# 04_MICROCONTROLLER.net
KiCad netlist of a schematic drawn in Altium Designer
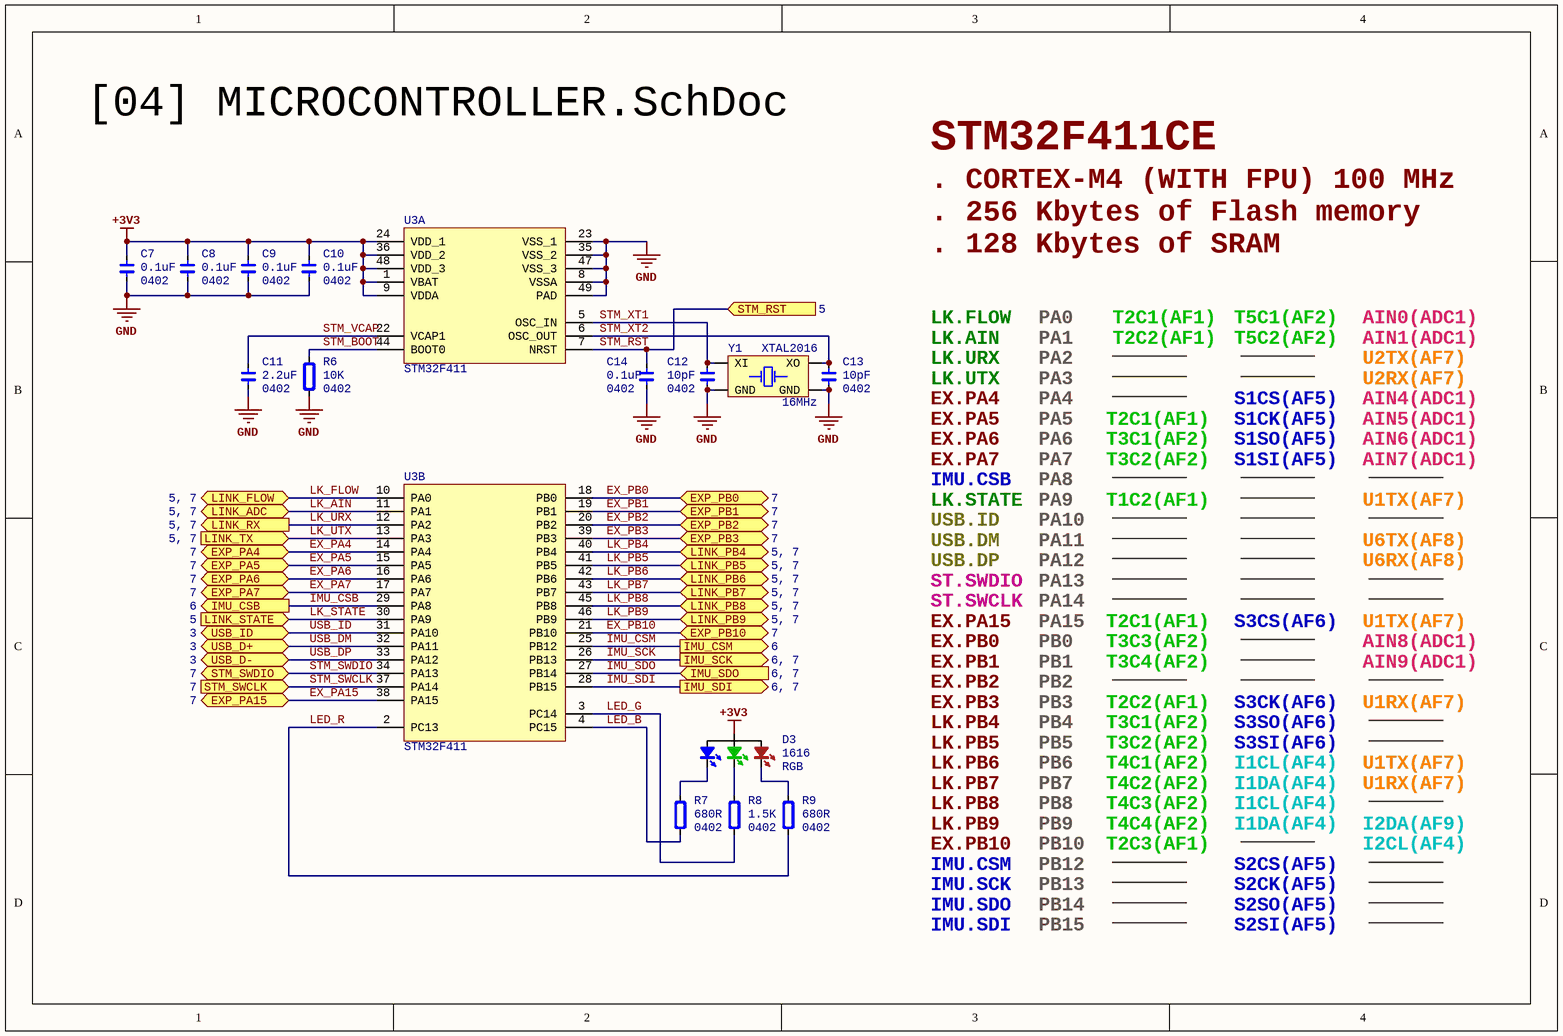
[diagram p0: [04] MICROCONTROLLER.SchDoc]

(export (version "E")
  (design (tool "Eeschema 10.0.6"))
  (components
    (comp (ref "C7")
      (value "0.1uF")
      (footprint "PCB_PassiveCap:CAP_0402")
      (description "Capacitor")
      (fields (field (name "TYPE") "0402") (field (name "Comment") "C0402"))
      (libsource (lib "SCH_Passive") (part "Cap_0402"))
    )
    (comp (ref "C8")
      (value "0.1uF")
      (footprint "PCB_PassiveCap:CAP_0402")
      (description "Capacitor")
      (fields (field (name "TYPE") "0402") (field (name "Comment") "C0402"))
      (libsource (lib "SCH_Passive") (part "Cap_0402"))
    )
    (comp (ref "C9")
      (value "0.1uF")
      (footprint "PCB_PassiveCap:CAP_0402")
      (description "Capacitor")
      (fields (field (name "TYPE") "0402") (field (name "Comment") "C0402"))
      (libsource (lib "SCH_Passive") (part "Cap_0402"))
    )
    (comp (ref "C10")
      (value "0.1uF")
      (footprint "PCB_PassiveCap:CAP_0402")
      (description "Capacitor")
      (fields (field (name "TYPE") "0402") (field (name "Comment") "C0402"))
      (libsource (lib "SCH_Passive") (part "Cap_0402"))
    )
    (comp (ref "C11")
      (value "2.2uF")
      (footprint "PCB_PassiveCap:CAP_0402")
      (description "Capacitor")
      (fields (field (name "TYPE") "0402") (field (name "Comment") "C0402"))
      (libsource (lib "SCH_Passive") (part "Cap_0402"))
    )
    (comp (ref "C12")
      (value "10pF")
      (footprint "PCB_PassiveCap:CAP_0402")
      (description "Capacitor")
      (fields (field (name "TYPE") "0402") (field (name "Comment") "C0402"))
      (libsource (lib "SCH_Passive") (part "Cap_0402"))
    )
    (comp (ref "C13")
      (value "10pF")
      (footprint "PCB_PassiveCap:CAP_0402")
      (description "Capacitor")
      (fields (field (name "TYPE") "0402") (field (name "Comment") "C0402"))
      (libsource (lib "SCH_Passive") (part "Cap_0402"))
    )
    (comp (ref "C14")
      (value "0.1uF")
      (footprint "PCB_PassiveCap:CAP_0402")
      (description "Capacitor")
      (fields (field (name "TYPE") "0402") (field (name "Comment") "C0402"))
      (libsource (lib "SCH_Passive") (part "Cap_0402"))
    )
    (comp (ref "D3")
      (value "RGB")
      (footprint "PCB_ActiveLED:LED_1616_RGB")
      (description "LED")
      (fields (field (name "TYPE") "1616"))
      (libsource (lib "SCH_Active") (part "LED_1616_RGB"))
    )
    (comp (ref "R6")
      (value "10K")
      (footprint "PCB_PassiveRes:RES_0402")
      (description "Resistor")
      (fields (field (name "TYPE") "0402") (field (name "Comment") "R0402"))
      (libsource (lib "SCH_Passive") (part "Res_0402"))
    )
    (comp (ref "R7")
      (value "680R")
      (footprint "PCB_PassiveRes:RES_0402")
      (description "Resistor")
      (fields (field (name "TYPE") "0402") (field (name "Comment") "R0402"))
      (libsource (lib "SCH_Passive") (part "Res_0402"))
    )
    (comp (ref "R8")
      (value "1.5K")
      (footprint "PCB_PassiveRes:RES_0402")
      (description "Resistor")
      (fields (field (name "TYPE") "0402") (field (name "Comment") "R0402"))
      (libsource (lib "SCH_Passive") (part "Res_0402"))
    )
    (comp (ref "R9")
      (value "680R")
      (footprint "PCB_PassiveRes:RES_0402")
      (description "Resistor")
      (fields (field (name "TYPE") "0402") (field (name "Comment") "R0402"))
      (libsource (lib "SCH_Passive") (part "Res_0402"))
    )
    (comp (ref "U3")
      (value "STM32F411")
      (footprint "PCB_IntegratedCircuit:QFN_P0.5_48")
      (description "MCU")
      (libsource (lib "SCH_IntegratedCircuit") (part "STM32F4x1C"))
    )
    (comp (ref "Y1")
      (value "16MHz")
      (footprint "PCB_Oscillator:XT_2016_4")
      (description "Crystal Oscillator")
      (fields (field (name "TYPE") "XTAL2016") (field (name "Comment") "XTAL2016"))
      (libsource (lib "SCH_Oscillator") (part "XTAL_2016_4P"))
    )
  )
  (nets
    (net (code "1") (name "+3V3") (class "Default")
      (node (ref "C10") (pin "2") (pinfunction "2_2") (pintype "passive"))
      (node (ref "C7") (pin "2") (pinfunction "2_2") (pintype "passive"))
      (node (ref "C8") (pin "2") (pinfunction "2_2") (pintype "passive"))
      (node (ref "C9") (pin "2") (pinfunction "2_2") (pintype "passive"))
      (node (ref "D3") (pin "4") (pinfunction "A_4") (pintype "passive"))
      (node (ref "U3") (pin "1") (pinfunction "VBAT_1") (pintype "passive"))
      (node (ref "U3") (pin "24") (pinfunction "VDD_1_24") (pintype "passive"))
      (node (ref "U3") (pin "36") (pinfunction "VDD_2_36") (pintype "passive"))
      (node (ref "U3") (pin "48") (pinfunction "VDD_3_48") (pintype "passive"))
      (node (ref "U3") (pin "9") (pinfunction "VDDA_9") (pintype "passive"))
    )
    (net (code "2") (name "/EX_PA4") (class "Default")
      (node (ref "U3") (pin "14") (pinfunction "PA4_14") (pintype "passive"))
    )
    (net (code "3") (name "/EX_PA5") (class "Default")
      (node (ref "U3") (pin "15") (pinfunction "PA5_15") (pintype "passive"))
    )
    (net (code "4") (name "/EX_PA6") (class "Default")
      (node (ref "U3") (pin "16") (pinfunction "PA6_16") (pintype "passive"))
    )
    (net (code "5") (name "/EX_PA7") (class "Default")
      (node (ref "U3") (pin "17") (pinfunction "PA7_17") (pintype "passive"))
    )
    (net (code "6") (name "/EX_PA15") (class "Default")
      (node (ref "U3") (pin "38") (pinfunction "PA15_38") (pintype "passive"))
    )
    (net (code "7") (name "/EX_PB0") (class "Default")
      (node (ref "U3") (pin "18") (pinfunction "PB0_18") (pintype "passive"))
    )
    (net (code "8") (name "/EX_PB1") (class "Default")
      (node (ref "U3") (pin "19") (pinfunction "PB1_19") (pintype "passive"))
    )
    (net (code "9") (name "/EX_PB2") (class "Default")
      (node (ref "U3") (pin "20") (pinfunction "PB2_20") (pintype "passive"))
    )
    (net (code "10") (name "/EX_PB3") (class "Default")
      (node (ref "U3") (pin "39") (pinfunction "PB3_39") (pintype "passive"))
    )
    (net (code "11") (name "/EX_PB10") (class "Default")
      (node (ref "U3") (pin "21") (pinfunction "PB10_21") (pintype "passive"))
    )
    (net (code "12") (name "/IMU_CSB") (class "Default")
      (node (ref "U3") (pin "29") (pinfunction "PA8_29") (pintype "passive"))
    )
    (net (code "13") (name "/IMU_CSM") (class "Default")
      (node (ref "U3") (pin "25") (pinfunction "PB12_25") (pintype "passive"))
    )
    (net (code "14") (name "/IMU_SCK") (class "Default")
      (node (ref "U3") (pin "26") (pinfunction "PB13_26") (pintype "passive"))
    )
    (net (code "15") (name "/IMU_SDI") (class "Default")
      (node (ref "U3") (pin "28") (pinfunction "PB15_28") (pintype "passive"))
    )
    (net (code "16") (name "/IMU_SDO") (class "Default")
      (node (ref "U3") (pin "27") (pinfunction "PB14_27") (pintype "passive"))
    )
    (net (code "17") (name "/LED_B") (class "Default")
      (node (ref "R7") (pin "1") (pinfunction "1_1") (pintype "passive"))
      (node (ref "U3") (pin "4") (pinfunction "PC15_4") (pintype "passive"))
    )
    (net (code "18") (name "/LED_G") (class "Default")
      (node (ref "R8") (pin "1") (pinfunction "1_1") (pintype "passive"))
      (node (ref "U3") (pin "3") (pinfunction "PC14_3") (pintype "passive"))
    )
    (net (code "19") (name "/LED_R") (class "Default")
      (node (ref "R9") (pin "1") (pinfunction "1_1") (pintype "passive"))
      (node (ref "U3") (pin "2") (pinfunction "PC13_2") (pintype "passive"))
    )
    (net (code "20") (name "/LK_AIN") (class "Default")
      (node (ref "U3") (pin "11") (pinfunction "PA1_11") (pintype "passive"))
    )
    (net (code "21") (name "/LK_FLOW") (class "Default")
      (node (ref "U3") (pin "10") (pinfunction "PA0_10") (pintype "passive"))
    )
    (net (code "22") (name "/LK_PB4") (class "Default")
      (node (ref "U3") (pin "40") (pinfunction "PB4_40") (pintype "passive"))
    )
    (net (code "23") (name "/LK_PB5") (class "Default")
      (node (ref "U3") (pin "41") (pinfunction "PB5_41") (pintype "passive"))
    )
    (net (code "24") (name "/LK_PB6") (class "Default")
      (node (ref "U3") (pin "42") (pinfunction "PB6_42") (pintype "passive"))
    )
    (net (code "25") (name "/LK_PB7") (class "Default")
      (node (ref "U3") (pin "43") (pinfunction "PB7_43") (pintype "passive"))
    )
    (net (code "26") (name "/LK_PB8") (class "Default")
      (node (ref "U3") (pin "45") (pinfunction "PB8_45") (pintype "passive"))
    )
    (net (code "27") (name "/LK_PB9") (class "Default")
      (node (ref "U3") (pin "46") (pinfunction "PB9_46") (pintype "passive"))
    )
    (net (code "28") (name "/LK_STATE") (class "Default")
      (node (ref "U3") (pin "30") (pinfunction "PA9_30") (pintype "passive"))
    )
    (net (code "29") (name "/LK_URX") (class "Default")
      (node (ref "U3") (pin "12") (pinfunction "PA2_12") (pintype "passive"))
    )
    (net (code "30") (name "/LK_UTX") (class "Default")
      (node (ref "U3") (pin "13") (pinfunction "PA3_13") (pintype "passive"))
    )
    (net (code "31") (name "/STM_BOOT") (class "Default")
      (node (ref "R6") (pin "2") (pinfunction "2_2") (pintype "passive"))
      (node (ref "U3") (pin "44") (pinfunction "BOOT0_44") (pintype "passive"))
    )
    (net (code "32") (name "/STM_RST") (class "Default")
      (node (ref "C14") (pin "2") (pinfunction "2_2") (pintype "passive"))
      (node (ref "U3") (pin "7") (pinfunction "NRST_7") (pintype "passive"))
    )
    (net (code "33") (name "/STM_SWCLK") (class "Default")
      (node (ref "U3") (pin "37") (pinfunction "PA14_37") (pintype "passive"))
    )
    (net (code "34") (name "/STM_SWDIO") (class "Default")
      (node (ref "U3") (pin "34") (pinfunction "PA13_34") (pintype "passive"))
    )
    (net (code "35") (name "/STM_VCAP") (class "Default")
      (node (ref "C11") (pin "2") (pinfunction "2_2") (pintype "passive"))
      (node (ref "U3") (pin "22") (pinfunction "VCAP1_22") (pintype "passive"))
    )
    (net (code "36") (name "/STM_XT1") (class "Default")
      (node (ref "C12") (pin "2") (pinfunction "2_2") (pintype "passive"))
      (node (ref "U3") (pin "5") (pinfunction "OSC_IN_5") (pintype "passive"))
      (node (ref "Y1") (pin "1") (pinfunction "XI_1") (pintype "passive"))
    )
    (net (code "37") (name "/STM_XT2") (class "Default")
      (node (ref "C13") (pin "2") (pinfunction "2_2") (pintype "passive"))
      (node (ref "U3") (pin "6") (pinfunction "OSC_OUT_6") (pintype "passive"))
      (node (ref "Y1") (pin "3") (pinfunction "XO_3") (pintype "passive"))
    )
    (net (code "38") (name "/USB_DM") (class "Default")
      (node (ref "U3") (pin "32") (pinfunction "PA11_32") (pintype "passive"))
    )
    (net (code "39") (name "/USB_DP") (class "Default")
      (node (ref "U3") (pin "33") (pinfunction "PA12_33") (pintype "passive"))
    )
    (net (code "40") (name "/USB_ID") (class "Default")
      (node (ref "U3") (pin "31") (pinfunction "PA10_31") (pintype "passive"))
    )
    (net (code "41") (name "GND") (class "Default")
      (node (ref "C10") (pin "1") (pinfunction "1_1") (pintype "passive"))
      (node (ref "C11") (pin "1") (pinfunction "1_1") (pintype "passive"))
      (node (ref "C12") (pin "1") (pinfunction "1_1") (pintype "passive"))
      (node (ref "C13") (pin "1") (pinfunction "1_1") (pintype "passive"))
      (node (ref "C14") (pin "1") (pinfunction "1_1") (pintype "passive"))
      (node (ref "C7") (pin "1") (pinfunction "1_1") (pintype "passive"))
      (node (ref "C8") (pin "1") (pinfunction "1_1") (pintype "passive"))
      (node (ref "C9") (pin "1") (pinfunction "1_1") (pintype "passive"))
      (node (ref "R6") (pin "1") (pinfunction "1_1") (pintype "passive"))
      (node (ref "U3") (pin "23") (pinfunction "VSS_1_23") (pintype "passive"))
      (node (ref "U3") (pin "35") (pinfunction "VSS_2_35") (pintype "passive"))
      (node (ref "U3") (pin "47") (pinfunction "VSS_3_47") (pintype "passive"))
      (node (ref "U3") (pin "49") (pinfunction "PAD_49") (pintype "passive"))
      (node (ref "U3") (pin "8") (pinfunction "VSSA_8") (pintype "passive"))
      (node (ref "Y1") (pin "2") (pinfunction "GND_2") (pintype "passive"))
      (node (ref "Y1") (pin "4") (pinfunction "GND_4") (pintype "passive"))
    )
    (net (code "42") (name "Net-(D3-B)") (class "Default")
      (node (ref "D3") (pin "3") (pinfunction "B_3") (pintype "passive"))
      (node (ref "R7") (pin "2") (pinfunction "2_2") (pintype "passive"))
    )
    (net (code "43") (name "Net-(D3-G)") (class "Default")
      (node (ref "D3") (pin "2") (pinfunction "G_2") (pintype "passive"))
      (node (ref "R8") (pin "2") (pinfunction "2_2") (pintype "passive"))
    )
    (net (code "44") (name "Net-(D3-R)") (class "Default")
      (node (ref "D3") (pin "1") (pinfunction "R_1") (pintype "passive"))
      (node (ref "R9") (pin "2") (pinfunction "2_2") (pintype "passive"))
    )
  )
)
